# Transmitter_PCB.net
KiCad netlist of a schematic drawn in Altium Designer
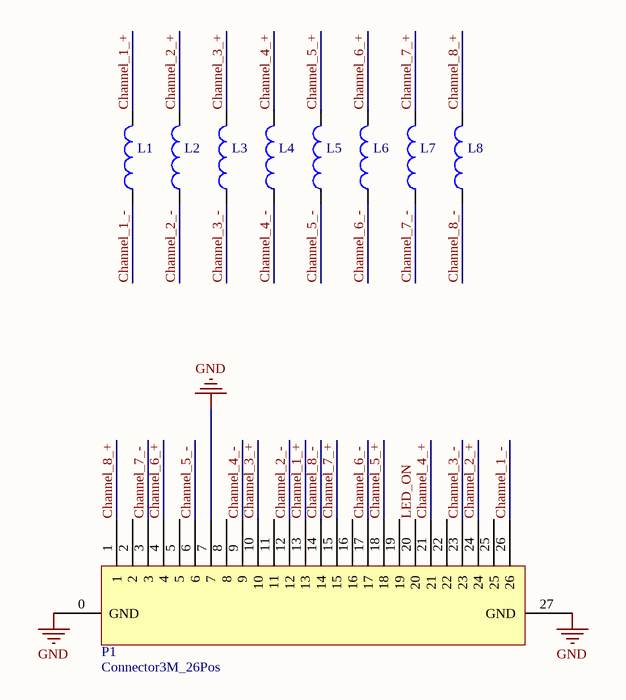
[diagram p0: Transmitter_PCB.SchDoc]

(export (version "E")
  (design (tool "Eeschema 10.0.6"))
  (components
    (comp (ref "L1")
      (value "~")
      (footprint "TRANSMITTER_COIL_UCC_ORIGINAL")
      (description "TRANSMITTER_COIL_UCC_ORIGINAL")
      (libsource (lib "Transmitter_PCB") (part "TRANSMITTER_COIL_UCC_ORIGINAL"))
    )
    (comp (ref "L2")
      (value "~")
      (footprint "TRANSMITTER_COIL_UCC_ORIGINAL")
      (description "TRANSMITTER_COIL_UCC_ORIGINAL")
      (libsource (lib "Transmitter_PCB") (part "TRANSMITTER_COIL_UCC_ORIGINAL"))
    )
    (comp (ref "L3")
      (value "~")
      (footprint "TRANSMITTER_COIL_UCC_ORIGINAL")
      (description "TRANSMITTER_COIL_UCC_ORIGINAL")
      (libsource (lib "Transmitter_PCB") (part "TRANSMITTER_COIL_UCC_ORIGINAL"))
    )
    (comp (ref "L4")
      (value "~")
      (footprint "TRANSMITTER_COIL_UCC_ORIGINAL")
      (description "TRANSMITTER_COIL_UCC_ORIGINAL")
      (libsource (lib "Transmitter_PCB") (part "TRANSMITTER_COIL_UCC_ORIGINAL"))
    )
    (comp (ref "L5")
      (value "~")
      (footprint "TRANSMITTER_COIL_UCC_ORIGINAL")
      (description "TRANSMITTER_COIL_UCC_ORIGINAL")
      (libsource (lib "Transmitter_PCB") (part "TRANSMITTER_COIL_UCC_ORIGINAL"))
    )
    (comp (ref "L6")
      (value "~")
      (footprint "TRANSMITTER_COIL_UCC_ORIGINAL")
      (description "TRANSMITTER_COIL_UCC_ORIGINAL")
      (libsource (lib "Transmitter_PCB") (part "TRANSMITTER_COIL_UCC_ORIGINAL"))
    )
    (comp (ref "L7")
      (value "~")
      (footprint "TRANSMITTER_COIL_UCC_ORIGINAL")
      (description "TRANSMITTER_COIL_UCC_ORIGINAL")
      (libsource (lib "Transmitter_PCB") (part "TRANSMITTER_COIL_UCC_ORIGINAL"))
    )
    (comp (ref "L8")
      (value "~")
      (footprint "TRANSMITTER_COIL_UCC_ORIGINAL")
      (description "TRANSMITTER_COIL_UCC_ORIGINAL")
      (libsource (lib "Transmitter_PCB") (part "TRANSMITTER_COIL_UCC_ORIGINAL"))
    )
    (comp (ref "P1")
      (value "Connector3M_26Pos")
      (footprint "Connector_3M_26Pos")
      (fields (field (name "PUBLISHER") "Altium Limited"))
      (libsource (lib "Transmitter_PCB") (part "Connector3M_26Pos"))
    )
  )
  (nets
    (net (code "1") (name "/Channel_1_+") (class "Default")
      (node (ref "L1") (pin "2") (pinfunction "2_2") (pintype "passive"))
      (node (ref "P1") (pin "13") (pinfunction "13_13") (pintype "passive"))
    )
    (net (code "2") (name "/Channel_1_-") (class "Default")
      (node (ref "L1") (pin "1") (pinfunction "1_1") (pintype "passive"))
      (node (ref "P1") (pin "26") (pinfunction "26_26") (pintype "passive"))
    )
    (net (code "3") (name "/Channel_2_+") (class "Default")
      (node (ref "L2") (pin "2") (pinfunction "2_2") (pintype "passive"))
      (node (ref "P1") (pin "24") (pinfunction "24_24") (pintype "passive"))
    )
    (net (code "4") (name "/Channel_2_-") (class "Default")
      (node (ref "L2") (pin "1") (pinfunction "1_1") (pintype "passive"))
      (node (ref "P1") (pin "12") (pinfunction "12_12") (pintype "passive"))
    )
    (net (code "5") (name "/Channel_3_+") (class "Default")
      (node (ref "L3") (pin "2") (pinfunction "2_2") (pintype "passive"))
      (node (ref "P1") (pin "10") (pinfunction "10_10") (pintype "passive"))
    )
    (net (code "6") (name "/Channel_3_-") (class "Default")
      (node (ref "L3") (pin "1") (pinfunction "1_1") (pintype "passive"))
      (node (ref "P1") (pin "23") (pinfunction "23_23") (pintype "passive"))
    )
    (net (code "7") (name "/Channel_4_+") (class "Default")
      (node (ref "L4") (pin "2") (pinfunction "2_2") (pintype "passive"))
      (node (ref "P1") (pin "21") (pinfunction "21_21") (pintype "passive"))
    )
    (net (code "8") (name "/Channel_4_-") (class "Default")
      (node (ref "L4") (pin "1") (pinfunction "1_1") (pintype "passive"))
      (node (ref "P1") (pin "9") (pinfunction "9_9") (pintype "passive"))
    )
    (net (code "9") (name "/Channel_5_+") (class "Default")
      (node (ref "L5") (pin "2") (pinfunction "2_2") (pintype "passive"))
      (node (ref "P1") (pin "18") (pinfunction "18_18") (pintype "passive"))
    )
    (net (code "10") (name "/Channel_5_-") (class "Default")
      (node (ref "L5") (pin "1") (pinfunction "1_1") (pintype "passive"))
      (node (ref "P1") (pin "6") (pinfunction "6_6") (pintype "passive"))
    )
    (net (code "11") (name "/Channel_6_+") (class "Default")
      (node (ref "L6") (pin "2") (pinfunction "2_2") (pintype "passive"))
      (node (ref "P1") (pin "4") (pinfunction "4_4") (pintype "passive"))
    )
    (net (code "12") (name "/Channel_6_-") (class "Default")
      (node (ref "L6") (pin "1") (pinfunction "1_1") (pintype "passive"))
      (node (ref "P1") (pin "17") (pinfunction "17_17") (pintype "passive"))
    )
    (net (code "13") (name "/Channel_7_+") (class "Default")
      (node (ref "L7") (pin "2") (pinfunction "2_2") (pintype "passive"))
      (node (ref "P1") (pin "15") (pinfunction "15_15") (pintype "passive"))
    )
    (net (code "14") (name "/Channel_7_-") (class "Default")
      (node (ref "L7") (pin "1") (pinfunction "1_1") (pintype "passive"))
      (node (ref "P1") (pin "3") (pinfunction "3_3") (pintype "passive"))
    )
    (net (code "15") (name "/Channel_8_+") (class "Default")
      (node (ref "L8") (pin "2") (pinfunction "2_2") (pintype "passive"))
      (node (ref "P1") (pin "1") (pinfunction "1_1") (pintype "passive"))
    )
    (net (code "16") (name "/Channel_8_-") (class "Default")
      (node (ref "L8") (pin "1") (pinfunction "1_1") (pintype "passive"))
      (node (ref "P1") (pin "14") (pinfunction "14_14") (pintype "passive"))
    )
    (net (code "17") (name "/LED_ON") (class "Default")
      (node (ref "P1") (pin "20") (pinfunction "20_20") (pintype "passive"))
    )
    (net (code "18") (name "GND") (class "Default")
      (node (ref "P1") (pin "0") (pinfunction "GND_0") (pintype "passive"))
      (node (ref "P1") (pin "27") (pinfunction "GND_27") (pintype "passive"))
      (node (ref "P1") (pin "7") (pinfunction "7_7") (pintype "passive"))
    )
    (net (code "19") (name "unconnected-(P1-Pad2)") (class "Default")
      (node (ref "P1") (pin "2") (pinfunction "2_2") (pintype "passive"))
    )
    (net (code "20") (name "unconnected-(P1-Pad5)") (class "Default")
      (node (ref "P1") (pin "5") (pinfunction "5_5") (pintype "passive"))
    )
    (net (code "21") (name "unconnected-(P1-Pad8)") (class "Default")
      (node (ref "P1") (pin "8") (pinfunction "8_8") (pintype "passive"))
    )
    (net (code "22") (name "unconnected-(P1-Pad11)") (class "Default")
      (node (ref "P1") (pin "11") (pinfunction "11_11") (pintype "passive"))
    )
    (net (code "23") (name "unconnected-(P1-Pad16)") (class "Default")
      (node (ref "P1") (pin "16") (pinfunction "16_16") (pintype "passive"))
    )
    (net (code "24") (name "unconnected-(P1-Pad19)") (class "Default")
      (node (ref "P1") (pin "19") (pinfunction "19_19") (pintype "passive"))
    )
    (net (code "25") (name "unconnected-(P1-Pad22)") (class "Default")
      (node (ref "P1") (pin "22") (pinfunction "22_22") (pintype "passive"))
    )
    (net (code "26") (name "unconnected-(P1-Pad25)") (class "Default")
      (node (ref "P1") (pin "25") (pinfunction "25_25") (pintype "passive"))
    )
  )
)
